# Reefing-IMU.net
KiCad netlist of a schematic drawn in Altium Designer
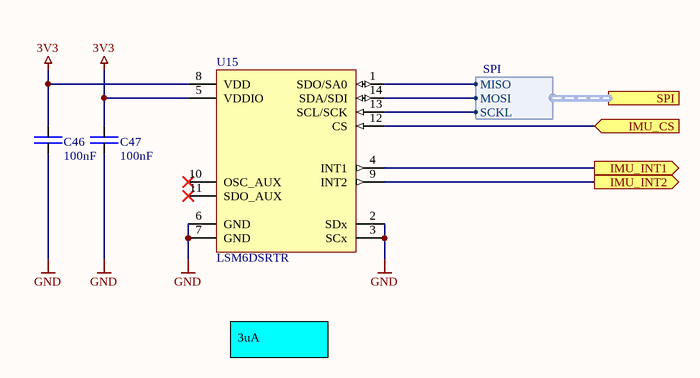
[diagram p0: Reefing-IMU.SchDoc]

(export (version "E")
  (design (tool "Eeschema 10.0.6"))
  (components
    (comp (ref "C46")
      (value "100nF")
      (footprint "SMD Keramikkondensator 0402")
      (description "SMD Ceramic Capacitor E6")
      (libsource (lib "CATS-EUROC") (part "E6 - 100nF"))
    )
    (comp (ref "C47")
      (value "100nF")
      (footprint "SMD Keramikkondensator 0402")
      (description "SMD Ceramic Capacitor E6")
      (libsource (lib "CATS-EUROC") (part "E6 - 100nF"))
    )
    (comp (ref "U15")
      (value "LSM6DSRTR")
      (footprint "SMD IC LGA-14")
      (description "Accelerometer, Gyroscope, Temperature, 6 Axis Sensor I²C, SPI Output")
      (libsource (lib "Sensors") (part "LSM6DSRTR"))
    )
  )
  (nets
    (net (code "2") (name "/IMU_CS") (class "Default")
      (node (ref "U15") (pin "12") (pinfunction "CS_12") (pintype "input"))
    )
    (net (code "3") (name "/IMU_INT1") (class "Default")
      (node (ref "U15") (pin "4") (pinfunction "INT1_4") (pintype "output"))
    )
    (net (code "4") (name "/IMU_INT2") (class "Default")
      (node (ref "U15") (pin "9") (pinfunction "INT2_9") (pintype "output"))
    )
    (net (code "5") (name "/MISO") (class "Default")
      (node (ref "U15") (pin "1") (pinfunction "SDO/SA0_1") (pintype "bidirectional"))
    )
    (net (code "6") (name "/MOSI") (class "Default")
      (node (ref "U15") (pin "14") (pinfunction "SDA/SDI_14") (pintype "bidirectional"))
    )
    (net (code "7") (name "/SCKL") (class "Default")
      (node (ref "U15") (pin "13") (pinfunction "SCL/SCK_13") (pintype "input"))
    )
    (net (code "9") (name "3V3") (class "Default")
      (node (ref "C46") (pin "2") (pinfunction "2_2") (pintype "passive"))
      (node (ref "C47") (pin "2") (pinfunction "2_2") (pintype "passive"))
      (node (ref "U15") (pin "5") (pinfunction "VDDIO_5") (pintype "passive"))
      (node (ref "U15") (pin "8") (pinfunction "VDD_8") (pintype "passive"))
    )
    (net (code "10") (name "GND") (class "Default")
      (node (ref "C46") (pin "1") (pinfunction "1_1") (pintype "passive"))
      (node (ref "C47") (pin "1") (pinfunction "1_1") (pintype "passive"))
      (node (ref "U15") (pin "2") (pinfunction "SDx_2") (pintype "passive"))
      (node (ref "U15") (pin "3") (pinfunction "SCx_3") (pintype "passive"))
      (node (ref "U15") (pin "6") (pinfunction "GND_6") (pintype "passive"))
      (node (ref "U15") (pin "7") (pinfunction "GND_7") (pintype "passive"))
    )
    (net (code "11") (name "unconnected-(U15-OSC_AUX-Pad10)") (class "Default")
      (node (ref "U15") (pin "10") (pinfunction "OSC_AUX_10") (pintype "passive+no_connect"))
    )
    (net (code "12") (name "unconnected-(U15-SDO_AUX-Pad11)") (class "Default")
      (node (ref "U15") (pin "11") (pinfunction "SDO_AUX_11") (pintype "passive+no_connect"))
    )
  )
)
